# nanopi_shield.net
KiCad netlist of a schematic drawn in EAGLE
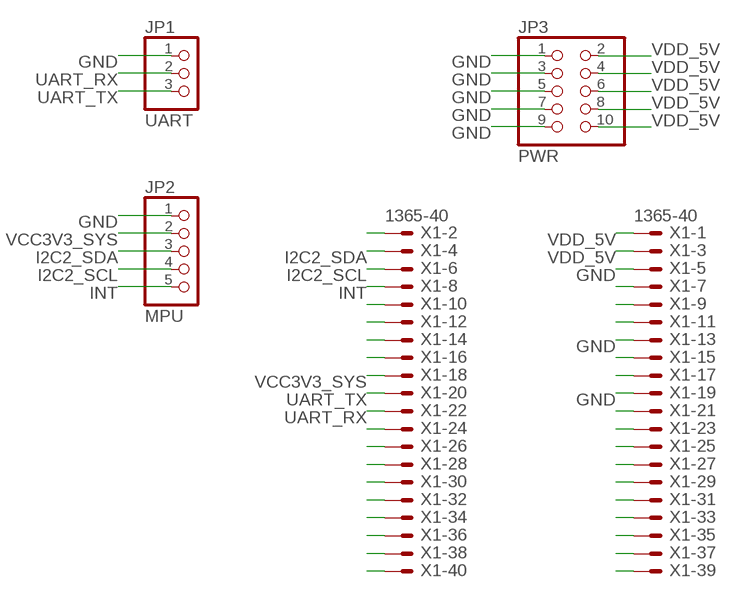
[diagram p0: schematic, sheet 1]

(export (version "E")
  (design (tool "Eeschema 10.0.6"))
  (components
    (comp (ref "JP1")
      (value "UART")
      (footprint "eagle-import:1X03")
      (libsource (lib "eagle-import") (part "PINHD-1X3"))
    )
    (comp (ref "JP2")
      (value "MPU")
      (footprint "eagle-import:1X05")
      (libsource (lib "eagle-import") (part "PINHD-1X5"))
    )
    (comp (ref "JP3")
      (value "PWR")
      (footprint "eagle-import:2X05")
      (libsource (lib "eagle-import") (part "PINHD-2X5"))
    )
    (comp (ref "X1")
      (value "1365-40")
      (footprint "eagle-import:1365-40")
      (libsource (lib "eagle-import") (part "1365-40"))
    )
  )
  (nets
    (net (code "1") (name "/GND") (class "Default")
      (node (ref "JP1") (pin "1") (pinfunction "1_1") (pintype "passive"))
      (node (ref "JP2") (pin "1") (pinfunction "1_1") (pintype "passive"))
      (node (ref "JP3") (pin "1") (pinfunction "1_1") (pintype "passive"))
      (node (ref "JP3") (pin "3") (pinfunction "3_3") (pintype "passive"))
      (node (ref "JP3") (pin "5") (pinfunction "5_5") (pintype "passive"))
      (node (ref "JP3") (pin "7") (pinfunction "7_7") (pintype "passive"))
      (node (ref "JP3") (pin "9") (pinfunction "9_9") (pintype "passive"))
      (node (ref "X1") (pin "13") (pinfunction "S_13") (pintype "passive"))
      (node (ref "X1") (pin "19") (pinfunction "S_19") (pintype "passive"))
      (node (ref "X1") (pin "5") (pinfunction "S_5") (pintype "passive"))
    )
    (net (code "2") (name "/I2C2_SCL") (class "Default")
      (node (ref "JP2") (pin "4") (pinfunction "4_4") (pintype "passive"))
      (node (ref "X1") (pin "6") (pinfunction "S_6") (pintype "passive"))
    )
    (net (code "3") (name "/I2C2_SDA") (class "Default")
      (node (ref "JP2") (pin "3") (pinfunction "3_3") (pintype "passive"))
      (node (ref "X1") (pin "4") (pinfunction "S_4") (pintype "passive"))
    )
    (net (code "4") (name "/INT") (class "Default")
      (node (ref "JP2") (pin "5") (pinfunction "5_5") (pintype "passive"))
      (node (ref "X1") (pin "8") (pinfunction "S_8") (pintype "passive"))
    )
    (net (code "5") (name "/UART_RX") (class "Default")
      (node (ref "JP1") (pin "2") (pinfunction "2_2") (pintype "passive"))
      (node (ref "X1") (pin "22") (pinfunction "S_22") (pintype "passive"))
    )
    (net (code "6") (name "/UART_TX") (class "Default")
      (node (ref "JP1") (pin "3") (pinfunction "3_3") (pintype "passive"))
      (node (ref "X1") (pin "20") (pinfunction "S_20") (pintype "passive"))
    )
    (net (code "7") (name "/VCC3V3_SYS") (class "Default")
      (node (ref "JP2") (pin "2") (pinfunction "2_2") (pintype "passive"))
      (node (ref "X1") (pin "18") (pinfunction "S_18") (pintype "passive"))
    )
    (net (code "8") (name "/VDD_5V") (class "Default")
      (node (ref "JP3") (pin "10") (pinfunction "10_10") (pintype "passive"))
      (node (ref "JP3") (pin "2") (pinfunction "2_2") (pintype "passive"))
      (node (ref "JP3") (pin "4") (pinfunction "4_4") (pintype "passive"))
      (node (ref "JP3") (pin "6") (pinfunction "6_6") (pintype "passive"))
      (node (ref "JP3") (pin "8") (pinfunction "8_8") (pintype "passive"))
      (node (ref "X1") (pin "1") (pinfunction "S_1") (pintype "passive"))
      (node (ref "X1") (pin "3") (pinfunction "S_3") (pintype "passive"))
    )
    (net (code "9") (name "unconnected-(X1AA-S-Pad33)") (class "Default")
      (node (ref "X1") (pin "33") (pinfunction "S_33") (pintype "passive"))
    )
    (net (code "10") (name "unconnected-(X1AB-S-Pad34)") (class "Default")
      (node (ref "X1") (pin "34") (pinfunction "S_34") (pintype "passive"))
    )
    (net (code "11") (name "unconnected-(X1AC-S-Pad35)") (class "Default")
      (node (ref "X1") (pin "35") (pinfunction "S_35") (pintype "passive"))
    )
    (net (code "12") (name "unconnected-(X1AD-S-Pad36)") (class "Default")
      (node (ref "X1") (pin "36") (pinfunction "S_36") (pintype "passive"))
    )
    (net (code "13") (name "unconnected-(X1AE-S-Pad37)") (class "Default")
      (node (ref "X1") (pin "37") (pinfunction "S_37") (pintype "passive"))
    )
    (net (code "14") (name "unconnected-(X1AF-S-Pad38)") (class "Default")
      (node (ref "X1") (pin "38") (pinfunction "S_38") (pintype "passive"))
    )
    (net (code "15") (name "unconnected-(X1AG-S-Pad39)") (class "Default")
      (node (ref "X1") (pin "39") (pinfunction "S_39") (pintype "passive"))
    )
    (net (code "16") (name "unconnected-(X1AI-S-Pad40)") (class "Default")
      (node (ref "X1") (pin "40") (pinfunction "S_40") (pintype "passive"))
    )
    (net (code "17") (name "unconnected-(X1AL-S-Pad7)") (class "Default")
      (node (ref "X1") (pin "7") (pinfunction "S_7") (pintype "passive"))
    )
    (net (code "18") (name "unconnected-(X1AN-S-Pad9)") (class "Default")
      (node (ref "X1") (pin "9") (pinfunction "S_9") (pintype "passive"))
    )
    (net (code "19") (name "unconnected-(X1B-S-Pad10)") (class "Default")
      (node (ref "X1") (pin "10") (pinfunction "S_10") (pintype "passive"))
    )
    (net (code "20") (name "unconnected-(X1C-S-Pad11)") (class "Default")
      (node (ref "X1") (pin "11") (pinfunction "S_11") (pintype "passive"))
    )
    (net (code "21") (name "unconnected-(X1D-S-Pad12)") (class "Default")
      (node (ref "X1") (pin "12") (pinfunction "S_12") (pintype "passive"))
    )
    (net (code "22") (name "unconnected-(X1F-S-Pad14)") (class "Default")
      (node (ref "X1") (pin "14") (pinfunction "S_14") (pintype "passive"))
    )
    (net (code "23") (name "unconnected-(X1G-S-Pad15)") (class "Default")
      (node (ref "X1") (pin "15") (pinfunction "S_15") (pintype "passive"))
    )
    (net (code "24") (name "unconnected-(X1H-S-Pad16)") (class "Default")
      (node (ref "X1") (pin "16") (pinfunction "S_16") (pintype "passive"))
    )
    (net (code "25") (name "unconnected-(X1I-S-Pad17)") (class "Default")
      (node (ref "X1") (pin "17") (pinfunction "S_17") (pintype "passive"))
    )
    (net (code "26") (name "unconnected-(X1L-S-Pad2)") (class "Default")
      (node (ref "X1") (pin "2") (pinfunction "S_2") (pintype "passive"))
    )
    (net (code "27") (name "unconnected-(X1N-S-Pad21)") (class "Default")
      (node (ref "X1") (pin "21") (pinfunction "S_21") (pintype "passive"))
    )
    (net (code "28") (name "unconnected-(X1P-S-Pad23)") (class "Default")
      (node (ref "X1") (pin "23") (pinfunction "S_23") (pintype "passive"))
    )
    (net (code "29") (name "unconnected-(X1Q-S-Pad24)") (class "Default")
      (node (ref "X1") (pin "24") (pinfunction "S_24") (pintype "passive"))
    )
    (net (code "30") (name "unconnected-(X1R-S-Pad25)") (class "Default")
      (node (ref "X1") (pin "25") (pinfunction "S_25") (pintype "passive"))
    )
    (net (code "31") (name "unconnected-(X1S-S-Pad26)") (class "Default")
      (node (ref "X1") (pin "26") (pinfunction "S_26") (pintype "passive"))
    )
    (net (code "32") (name "unconnected-(X1T-S-Pad27)") (class "Default")
      (node (ref "X1") (pin "27") (pinfunction "S_27") (pintype "passive"))
    )
    (net (code "33") (name "unconnected-(X1U-S-Pad28)") (class "Default")
      (node (ref "X1") (pin "28") (pinfunction "S_28") (pintype "passive"))
    )
    (net (code "34") (name "unconnected-(X1V-S-Pad29)") (class "Default")
      (node (ref "X1") (pin "29") (pinfunction "S_29") (pintype "passive"))
    )
    (net (code "35") (name "unconnected-(X1X-S-Pad30)") (class "Default")
      (node (ref "X1") (pin "30") (pinfunction "S_30") (pintype "passive"))
    )
    (net (code "36") (name "unconnected-(X1Y-S-Pad31)") (class "Default")
      (node (ref "X1") (pin "31") (pinfunction "S_31") (pintype "passive"))
    )
    (net (code "37") (name "unconnected-(X1Z-S-Pad32)") (class "Default")
      (node (ref "X1") (pin "32") (pinfunction "S_32") (pintype "passive"))
    )
  )
)
